# pca9535bowing.net
KiCad netlist of a schematic drawn in EAGLE
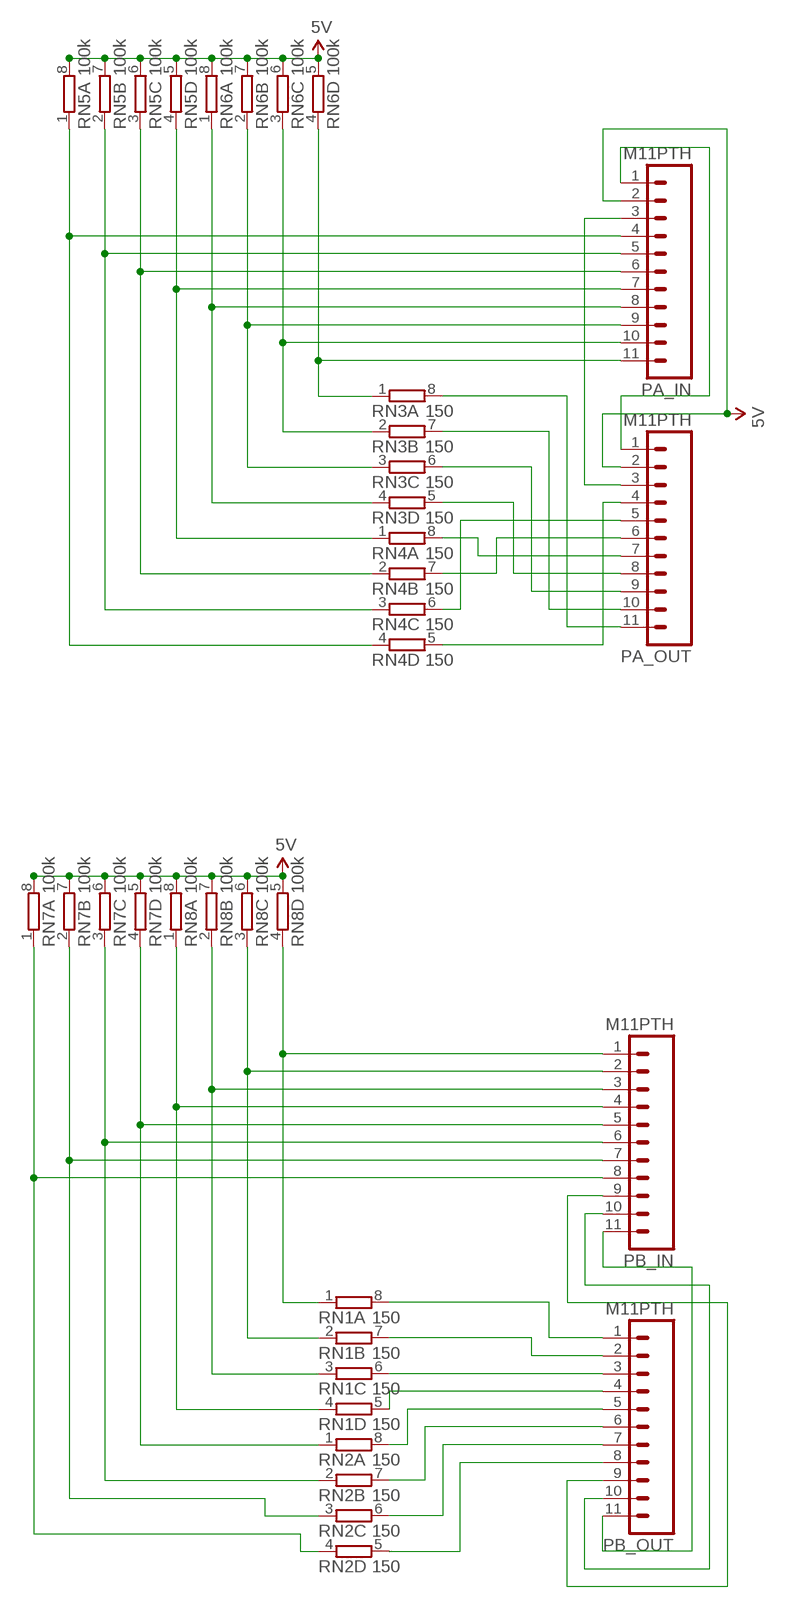
[diagram p0: schematic, sheet 1]

(export (version "E")
  (design (tool "Eeschema 10.0.6"))
  (components
    (comp (ref "PA_IN")
      (value "M11PTH")
      (footprint "eagle-import:1X11")
      (libsource (lib "eagle-import") (part "M11PTH"))
    )
    (comp (ref "PA_OUT")
      (value "M11PTH")
      (footprint "eagle-import:1X11")
      (libsource (lib "eagle-import") (part "M11PTH"))
    )
    (comp (ref "PB_IN")
      (value "M11PTH")
      (footprint "eagle-import:1X11")
      (libsource (lib "eagle-import") (part "M11PTH"))
    )
    (comp (ref "PB_OUT")
      (value "M11PTH")
      (footprint "eagle-import:1X11")
      (libsource (lib "eagle-import") (part "M11PTH"))
    )
    (comp (ref "RN1")
      (value "150")
      (footprint "eagle-import:CAY16")
      (libsource (lib "eagle-import") (part "4R-NCAY16"))
    )
    (comp (ref "RN2")
      (value "150")
      (footprint "eagle-import:CAY16")
      (libsource (lib "eagle-import") (part "4R-NCAY16"))
    )
    (comp (ref "RN3")
      (value "150")
      (footprint "eagle-import:CAY16")
      (libsource (lib "eagle-import") (part "4R-NCAY16"))
    )
    (comp (ref "RN4")
      (value "150")
      (footprint "eagle-import:CAY16")
      (libsource (lib "eagle-import") (part "4R-NCAY16"))
    )
    (comp (ref "RN5")
      (value "100k")
      (footprint "eagle-import:CAY16")
      (libsource (lib "eagle-import") (part "4R-NCAY16"))
    )
    (comp (ref "RN6")
      (value "100k")
      (footprint "eagle-import:CAY16")
      (libsource (lib "eagle-import") (part "4R-NCAY16"))
    )
    (comp (ref "RN7")
      (value "100k")
      (footprint "eagle-import:CAY16")
      (libsource (lib "eagle-import") (part "4R-NCAY16"))
    )
    (comp (ref "RN8")
      (value "100k")
      (footprint "eagle-import:CAY16")
      (libsource (lib "eagle-import") (part "4R-NCAY16"))
    )
  )
  (nets
    (net (code "1") (name "5V") (class "Default")
      (node (ref "PA_IN") (pin "2") (pinfunction "2_2") (pintype "passive"))
      (node (ref "PA_OUT") (pin "2") (pinfunction "2_2") (pintype "passive"))
      (node (ref "RN5") (pin "5") (pinfunction "2_5") (pintype "passive"))
      (node (ref "RN5") (pin "6") (pinfunction "2_6") (pintype "passive"))
      (node (ref "RN5") (pin "7") (pinfunction "2_7") (pintype "passive"))
      (node (ref "RN5") (pin "8") (pinfunction "2_8") (pintype "passive"))
      (node (ref "RN6") (pin "5") (pinfunction "2_5") (pintype "passive"))
      (node (ref "RN6") (pin "6") (pinfunction "2_6") (pintype "passive"))
      (node (ref "RN6") (pin "7") (pinfunction "2_7") (pintype "passive"))
      (node (ref "RN6") (pin "8") (pinfunction "2_8") (pintype "passive"))
      (node (ref "RN7") (pin "5") (pinfunction "2_5") (pintype "passive"))
      (node (ref "RN7") (pin "6") (pinfunction "2_6") (pintype "passive"))
      (node (ref "RN7") (pin "7") (pinfunction "2_7") (pintype "passive"))
      (node (ref "RN7") (pin "8") (pinfunction "2_8") (pintype "passive"))
      (node (ref "RN8") (pin "5") (pinfunction "2_5") (pintype "passive"))
      (node (ref "RN8") (pin "6") (pinfunction "2_6") (pintype "passive"))
      (node (ref "RN8") (pin "7") (pinfunction "2_7") (pintype "passive"))
      (node (ref "RN8") (pin "8") (pinfunction "2_8") (pintype "passive"))
    )
    (net (code "2") (name "Net-(PA_IN-Pad1)") (class "Default")
      (node (ref "PA_IN") (pin "1") (pinfunction "1_1") (pintype "passive"))
      (node (ref "PA_OUT") (pin "1") (pinfunction "1_1") (pintype "passive"))
    )
    (net (code "3") (name "Net-(PA_IN-Pad3)") (class "Default")
      (node (ref "PA_IN") (pin "3") (pinfunction "3_3") (pintype "passive"))
      (node (ref "PA_OUT") (pin "3") (pinfunction "3_3") (pintype "passive"))
    )
    (net (code "4") (name "Net-(PB_IN-Pad9)") (class "Default")
      (node (ref "PB_IN") (pin "9") (pinfunction "9_9") (pintype "passive"))
      (node (ref "PB_OUT") (pin "9") (pinfunction "9_9") (pintype "passive"))
    )
    (net (code "5") (name "Net-(PB_IN-Pad10)") (class "Default")
      (node (ref "PB_IN") (pin "10") (pinfunction "10_10") (pintype "passive"))
      (node (ref "PB_OUT") (pin "10") (pinfunction "10_10") (pintype "passive"))
    )
    (net (code "6") (name "Net-(PB_IN-Pad11)") (class "Default")
      (node (ref "PB_IN") (pin "11") (pinfunction "11_11") (pintype "passive"))
      (node (ref "PB_OUT") (pin "11") (pinfunction "11_11") (pintype "passive"))
    )
    (net (code "7") (name "Net-(RN1A-2)") (class "Default")
      (node (ref "PB_OUT") (pin "1") (pinfunction "1_1") (pintype "passive"))
      (node (ref "RN1") (pin "8") (pinfunction "2_8") (pintype "passive"))
    )
    (net (code "8") (name "Net-(RN1B-1)") (class "Default")
      (node (ref "PB_IN") (pin "2") (pinfunction "2_2") (pintype "passive"))
      (node (ref "RN1") (pin "2") (pinfunction "1_2") (pintype "passive"))
      (node (ref "RN8") (pin "3") (pinfunction "1_3") (pintype "passive"))
    )
    (net (code "9") (name "Net-(RN1B-2)") (class "Default")
      (node (ref "PB_OUT") (pin "2") (pinfunction "2_2") (pintype "passive"))
      (node (ref "RN1") (pin "7") (pinfunction "2_7") (pintype "passive"))
    )
    (net (code "10") (name "Net-(RN1C-1)") (class "Default")
      (node (ref "PB_IN") (pin "3") (pinfunction "3_3") (pintype "passive"))
      (node (ref "RN1") (pin "3") (pinfunction "1_3") (pintype "passive"))
      (node (ref "RN8") (pin "2") (pinfunction "1_2") (pintype "passive"))
    )
    (net (code "11") (name "Net-(RN1C-2)") (class "Default")
      (node (ref "PB_OUT") (pin "3") (pinfunction "3_3") (pintype "passive"))
      (node (ref "RN1") (pin "6") (pinfunction "2_6") (pintype "passive"))
    )
    (net (code "12") (name "Net-(RN1D-1)") (class "Default")
      (node (ref "PB_IN") (pin "4") (pinfunction "4_4") (pintype "passive"))
      (node (ref "RN1") (pin "4") (pinfunction "1_4") (pintype "passive"))
      (node (ref "RN8") (pin "1") (pinfunction "1_1") (pintype "passive"))
    )
    (net (code "13") (name "Net-(RN1D-2)") (class "Default")
      (node (ref "PB_OUT") (pin "4") (pinfunction "4_4") (pintype "passive"))
      (node (ref "RN1") (pin "5") (pinfunction "2_5") (pintype "passive"))
    )
    (net (code "14") (name "Net-(RN2A-2)") (class "Default")
      (node (ref "PB_OUT") (pin "5") (pinfunction "5_5") (pintype "passive"))
      (node (ref "RN2") (pin "8") (pinfunction "2_8") (pintype "passive"))
    )
    (net (code "15") (name "Net-(RN2B-1)") (class "Default")
      (node (ref "PB_IN") (pin "6") (pinfunction "6_6") (pintype "passive"))
      (node (ref "RN2") (pin "2") (pinfunction "1_2") (pintype "passive"))
      (node (ref "RN7") (pin "3") (pinfunction "1_3") (pintype "passive"))
    )
    (net (code "16") (name "Net-(RN2B-2)") (class "Default")
      (node (ref "PB_OUT") (pin "6") (pinfunction "6_6") (pintype "passive"))
      (node (ref "RN2") (pin "7") (pinfunction "2_7") (pintype "passive"))
    )
    (net (code "17") (name "Net-(RN2C-1)") (class "Default")
      (node (ref "PB_IN") (pin "7") (pinfunction "7_7") (pintype "passive"))
      (node (ref "RN2") (pin "3") (pinfunction "1_3") (pintype "passive"))
      (node (ref "RN7") (pin "2") (pinfunction "1_2") (pintype "passive"))
    )
    (net (code "18") (name "Net-(RN2C-2)") (class "Default")
      (node (ref "PB_OUT") (pin "7") (pinfunction "7_7") (pintype "passive"))
      (node (ref "RN2") (pin "6") (pinfunction "2_6") (pintype "passive"))
    )
    (net (code "19") (name "Net-(RN2D-1)") (class "Default")
      (node (ref "PB_IN") (pin "8") (pinfunction "8_8") (pintype "passive"))
      (node (ref "RN2") (pin "4") (pinfunction "1_4") (pintype "passive"))
      (node (ref "RN7") (pin "1") (pinfunction "1_1") (pintype "passive"))
    )
    (net (code "20") (name "Net-(RN2D-2)") (class "Default")
      (node (ref "PB_OUT") (pin "8") (pinfunction "8_8") (pintype "passive"))
      (node (ref "RN2") (pin "5") (pinfunction "2_5") (pintype "passive"))
    )
    (net (code "21") (name "Net-(RN3A-2)") (class "Default")
      (node (ref "PA_OUT") (pin "11") (pinfunction "11_11") (pintype "passive"))
      (node (ref "RN3") (pin "8") (pinfunction "2_8") (pintype "passive"))
    )
    (net (code "22") (name "Net-(RN3B-1)") (class "Default")
      (node (ref "PA_IN") (pin "10") (pinfunction "10_10") (pintype "passive"))
      (node (ref "RN3") (pin "2") (pinfunction "1_2") (pintype "passive"))
      (node (ref "RN6") (pin "3") (pinfunction "1_3") (pintype "passive"))
    )
    (net (code "23") (name "Net-(RN3B-2)") (class "Default")
      (node (ref "PA_OUT") (pin "10") (pinfunction "10_10") (pintype "passive"))
      (node (ref "RN3") (pin "7") (pinfunction "2_7") (pintype "passive"))
    )
    (net (code "24") (name "Net-(RN3C-1)") (class "Default")
      (node (ref "PA_IN") (pin "9") (pinfunction "9_9") (pintype "passive"))
      (node (ref "RN3") (pin "3") (pinfunction "1_3") (pintype "passive"))
      (node (ref "RN6") (pin "2") (pinfunction "1_2") (pintype "passive"))
    )
    (net (code "25") (name "Net-(RN3C-2)") (class "Default")
      (node (ref "PA_OUT") (pin "9") (pinfunction "9_9") (pintype "passive"))
      (node (ref "RN3") (pin "6") (pinfunction "2_6") (pintype "passive"))
    )
    (net (code "26") (name "Net-(RN3D-1)") (class "Default")
      (node (ref "PA_IN") (pin "8") (pinfunction "8_8") (pintype "passive"))
      (node (ref "RN3") (pin "4") (pinfunction "1_4") (pintype "passive"))
      (node (ref "RN6") (pin "1") (pinfunction "1_1") (pintype "passive"))
    )
    (net (code "27") (name "Net-(RN3D-2)") (class "Default")
      (node (ref "PA_OUT") (pin "8") (pinfunction "8_8") (pintype "passive"))
      (node (ref "RN3") (pin "5") (pinfunction "2_5") (pintype "passive"))
    )
    (net (code "28") (name "Net-(RN4A-2)") (class "Default")
      (node (ref "PA_OUT") (pin "7") (pinfunction "7_7") (pintype "passive"))
      (node (ref "RN4") (pin "8") (pinfunction "2_8") (pintype "passive"))
    )
    (net (code "29") (name "Net-(RN4B-1)") (class "Default")
      (node (ref "PA_IN") (pin "6") (pinfunction "6_6") (pintype "passive"))
      (node (ref "RN4") (pin "2") (pinfunction "1_2") (pintype "passive"))
      (node (ref "RN5") (pin "3") (pinfunction "1_3") (pintype "passive"))
    )
    (net (code "30") (name "Net-(RN4B-2)") (class "Default")
      (node (ref "PA_OUT") (pin "6") (pinfunction "6_6") (pintype "passive"))
      (node (ref "RN4") (pin "7") (pinfunction "2_7") (pintype "passive"))
    )
    (net (code "31") (name "Net-(RN4C-1)") (class "Default")
      (node (ref "PA_IN") (pin "5") (pinfunction "5_5") (pintype "passive"))
      (node (ref "RN4") (pin "3") (pinfunction "1_3") (pintype "passive"))
      (node (ref "RN5") (pin "2") (pinfunction "1_2") (pintype "passive"))
    )
    (net (code "32") (name "Net-(RN4C-2)") (class "Default")
      (node (ref "PA_OUT") (pin "5") (pinfunction "5_5") (pintype "passive"))
      (node (ref "RN4") (pin "6") (pinfunction "2_6") (pintype "passive"))
    )
    (net (code "33") (name "Net-(RN4D-1)") (class "Default")
      (node (ref "PA_IN") (pin "4") (pinfunction "4_4") (pintype "passive"))
      (node (ref "RN4") (pin "4") (pinfunction "1_4") (pintype "passive"))
      (node (ref "RN5") (pin "1") (pinfunction "1_1") (pintype "passive"))
    )
    (net (code "34") (name "Net-(RN4D-2)") (class "Default")
      (node (ref "PA_OUT") (pin "4") (pinfunction "4_4") (pintype "passive"))
      (node (ref "RN4") (pin "5") (pinfunction "2_5") (pintype "passive"))
    )
    (net (code "35") (name "Net-(RN5D-1)") (class "Default")
      (node (ref "PA_IN") (pin "7") (pinfunction "7_7") (pintype "passive"))
      (node (ref "RN4") (pin "1") (pinfunction "1_1") (pintype "passive"))
      (node (ref "RN5") (pin "4") (pinfunction "1_4") (pintype "passive"))
    )
    (net (code "36") (name "Net-(RN6D-1)") (class "Default")
      (node (ref "PA_IN") (pin "11") (pinfunction "11_11") (pintype "passive"))
      (node (ref "RN3") (pin "1") (pinfunction "1_1") (pintype "passive"))
      (node (ref "RN6") (pin "4") (pinfunction "1_4") (pintype "passive"))
    )
    (net (code "37") (name "Net-(RN7D-1)") (class "Default")
      (node (ref "PB_IN") (pin "5") (pinfunction "5_5") (pintype "passive"))
      (node (ref "RN2") (pin "1") (pinfunction "1_1") (pintype "passive"))
      (node (ref "RN7") (pin "4") (pinfunction "1_4") (pintype "passive"))
    )
    (net (code "38") (name "Net-(RN8D-1)") (class "Default")
      (node (ref "PB_IN") (pin "1") (pinfunction "1_1") (pintype "passive"))
      (node (ref "RN1") (pin "1") (pinfunction "1_1") (pintype "passive"))
      (node (ref "RN8") (pin "4") (pinfunction "1_4") (pintype "passive"))
    )
  )
)
